# lower.net
KiCad netlist of a schematic drawn in EAGLE
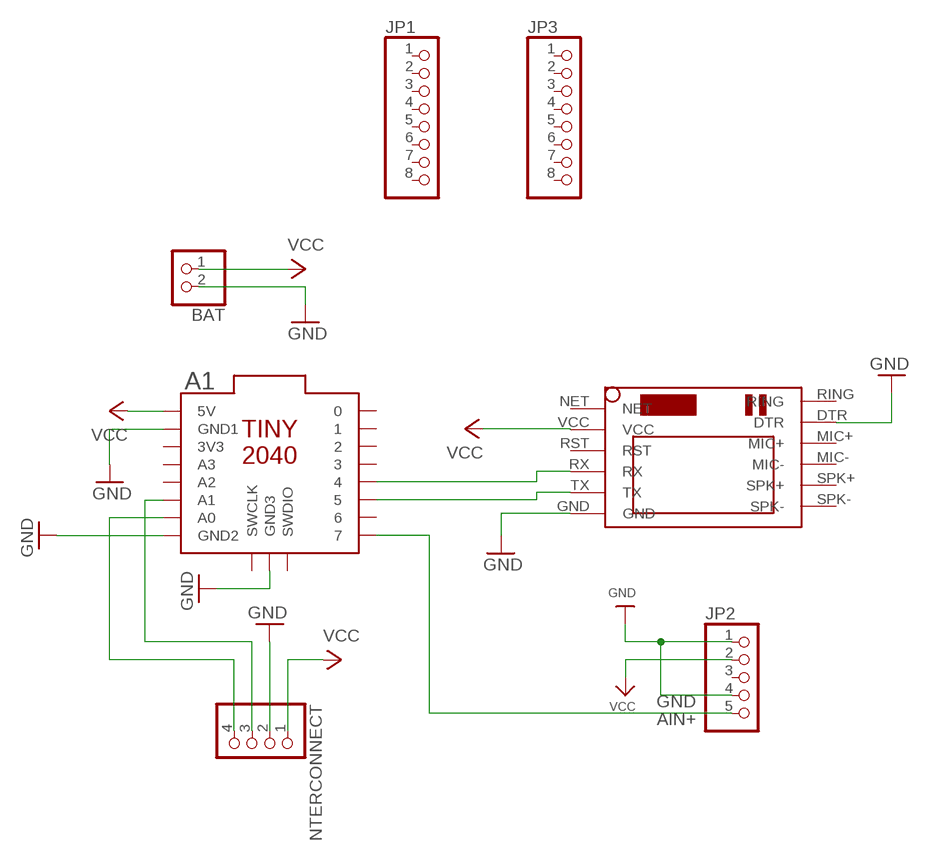
[diagram p0: schematic, sheet 1]

(export (version "E")
  (design (tool "Eeschema 10.0.6"))
  (components
    (comp (ref "A1")
      (value "TINY2040")
      (footprint "eagle-import:TINY2040")
      (libsource (lib "eagle-import") (part "TINY2040"))
    )
    (comp (ref "BAT")
      (value "JST_2PIN-THM-RA")
      (footprint "eagle-import:JST-PH-2-THM-RA")
      (libsource (lib "eagle-import") (part "JST_2PIN-THM-RA"))
    )
    (comp (ref "INTERCONNECT")
      (value "PINHD-1X4")
      (footprint "eagle-import:1X04")
      (libsource (lib "eagle-import") (part "PINHD-1X4"))
    )
    (comp (ref "JP1")
      (value "PINHD-1X8")
      (footprint "eagle-import:1X08")
      (libsource (lib "eagle-import") (part "PINHD-1X8"))
    )
    (comp (ref "JP2")
      (value "HEADER-1X570MIL")
      (footprint "eagle-import:1X05_ROUND_70")
      (libsource (lib "eagle-import") (part "HEADER-1X570MIL"))
    )
    (comp (ref "JP3")
      (value "PINHD-1X8")
      (footprint "eagle-import:1X08")
      (libsource (lib "eagle-import") (part "PINHD-1X8"))
    )
    (comp (ref "U$2")
      (value "SIM800LMODULE")
      (footprint "eagle-import:SIM800LMODULE")
      (libsource (lib "eagle-import") (part "SIM800LMODULE"))
    )
  )
  (nets
    (net (code "1") (name "/AIN+") (class "Default")
      (node (ref "A1") (pin "7") (pinfunction "7_7") (pintype "bidirectional"))
      (node (ref "JP2") (pin "5") (pinfunction "5_5") (pintype "passive"))
    )
    (net (code "2") (name "GND") (class "Default")
      (node (ref "A1") (pin "GND1") (pinfunction "GND1_GND1") (pintype "bidirectional"))
      (node (ref "A1") (pin "GND2") (pinfunction "GND2_GND2") (pintype "bidirectional"))
      (node (ref "A1") (pin "GND3") (pinfunction "GND3_GND3") (pintype "bidirectional"))
      (node (ref "BAT") (pin "2") (pinfunction "1_2") (pintype "passive"))
      (node (ref "INTERCONNECT") (pin "2") (pinfunction "2_2") (pintype "passive"))
      (node (ref "JP2") (pin "1") (pinfunction "1_1") (pintype "passive"))
      (node (ref "JP2") (pin "4") (pinfunction "4_4") (pintype "passive"))
      (node (ref "U$2") (pin "DTR") (pinfunction "DTR_DTR") (pintype "bidirectional"))
      (node (ref "U$2") (pin "GND") (pinfunction "GND_GND") (pintype "bidirectional"))
    )
    (net (code "3") (name "Net-(A1-Pad4)") (class "Default")
      (node (ref "A1") (pin "4") (pinfunction "4_4") (pintype "bidirectional"))
      (node (ref "U$2") (pin "RX") (pinfunction "RX_RX") (pintype "bidirectional"))
    )
    (net (code "4") (name "Net-(A1-Pad5)") (class "Default")
      (node (ref "A1") (pin "5") (pinfunction "5_5") (pintype "bidirectional"))
      (node (ref "U$2") (pin "TX") (pinfunction "TX_TX") (pintype "bidirectional"))
    )
    (net (code "5") (name "Net-(A1-PadA0)") (class "Default")
      (node (ref "A1") (pin "A0") (pinfunction "A0_A0") (pintype "bidirectional"))
      (node (ref "INTERCONNECT") (pin "4") (pinfunction "4_4") (pintype "passive"))
    )
    (net (code "6") (name "Net-(A1-PadA1)") (class "Default")
      (node (ref "A1") (pin "A1") (pinfunction "A1_A1") (pintype "bidirectional"))
      (node (ref "INTERCONNECT") (pin "3") (pinfunction "3_3") (pintype "passive"))
    )
    (net (code "7") (name "VCC") (class "Default")
      (node (ref "A1") (pin "5V") (pinfunction "5V_5V") (pintype "bidirectional"))
      (node (ref "BAT") (pin "1") (pinfunction "2_1") (pintype "passive"))
      (node (ref "INTERCONNECT") (pin "1") (pinfunction "1_1") (pintype "passive"))
      (node (ref "JP2") (pin "2") (pinfunction "2_2") (pintype "passive"))
      (node (ref "U$2") (pin "VCC") (pinfunction "VCC_VCC") (pintype "bidirectional"))
    )
    (net (code "8") (name "unconnected-(A1-Pad0)") (class "Default")
      (node (ref "A1") (pin "0") (pinfunction "0_0") (pintype "bidirectional"))
    )
    (net (code "9") (name "unconnected-(A1-Pad1)") (class "Default")
      (node (ref "A1") (pin "1") (pinfunction "1_1") (pintype "bidirectional"))
    )
    (net (code "10") (name "unconnected-(A1-Pad2)") (class "Default")
      (node (ref "A1") (pin "2") (pinfunction "2_2") (pintype "bidirectional"))
    )
    (net (code "11") (name "unconnected-(A1-Pad3)") (class "Default")
      (node (ref "A1") (pin "3") (pinfunction "3_3") (pintype "bidirectional"))
    )
    (net (code "12") (name "unconnected-(A1-Pad3V3)") (class "Default")
      (node (ref "A1") (pin "3V3") (pinfunction "3V3_3V3") (pintype "bidirectional"))
    )
    (net (code "13") (name "unconnected-(A1-Pad6)") (class "Default")
      (node (ref "A1") (pin "6") (pinfunction "6_6") (pintype "bidirectional"))
    )
    (net (code "14") (name "unconnected-(A1-PadA2)") (class "Default")
      (node (ref "A1") (pin "A2") (pinfunction "A2_A2") (pintype "bidirectional"))
    )
    (net (code "15") (name "unconnected-(A1-PadA3)") (class "Default")
      (node (ref "A1") (pin "A3") (pinfunction "A3_A3") (pintype "bidirectional"))
    )
    (net (code "16") (name "unconnected-(A1-PadSWCLK)") (class "Default")
      (node (ref "A1") (pin "SWCLK") (pinfunction "SWCLK_SWCLK") (pintype "bidirectional"))
    )
    (net (code "17") (name "unconnected-(A1-PadSWDIO)") (class "Default")
      (node (ref "A1") (pin "SWDIO") (pinfunction "SWDIO_SWDIO") (pintype "bidirectional"))
    )
    (net (code "18") (name "unconnected-(JP1-Pad1)") (class "Default")
      (node (ref "JP1") (pin "1") (pinfunction "1_1") (pintype "passive"))
    )
    (net (code "19") (name "unconnected-(JP1-Pad2)") (class "Default")
      (node (ref "JP1") (pin "2") (pinfunction "2_2") (pintype "passive"))
    )
    (net (code "20") (name "unconnected-(JP1-Pad3)") (class "Default")
      (node (ref "JP1") (pin "3") (pinfunction "3_3") (pintype "passive"))
    )
    (net (code "21") (name "unconnected-(JP1-Pad4)") (class "Default")
      (node (ref "JP1") (pin "4") (pinfunction "4_4") (pintype "passive"))
    )
    (net (code "22") (name "unconnected-(JP1-Pad5)") (class "Default")
      (node (ref "JP1") (pin "5") (pinfunction "5_5") (pintype "passive"))
    )
    (net (code "23") (name "unconnected-(JP1-Pad6)") (class "Default")
      (node (ref "JP1") (pin "6") (pinfunction "6_6") (pintype "passive"))
    )
    (net (code "24") (name "unconnected-(JP1-Pad7)") (class "Default")
      (node (ref "JP1") (pin "7") (pinfunction "7_7") (pintype "passive"))
    )
    (net (code "25") (name "unconnected-(JP1-Pad8)") (class "Default")
      (node (ref "JP1") (pin "8") (pinfunction "8_8") (pintype "passive"))
    )
    (net (code "26") (name "unconnected-(JP2-Pad3)") (class "Default")
      (node (ref "JP2") (pin "3") (pinfunction "3_3") (pintype "passive"))
    )
    (net (code "27") (name "unconnected-(JP3-Pad1)") (class "Default")
      (node (ref "JP3") (pin "1") (pinfunction "1_1") (pintype "passive"))
    )
    (net (code "28") (name "unconnected-(JP3-Pad2)") (class "Default")
      (node (ref "JP3") (pin "2") (pinfunction "2_2") (pintype "passive"))
    )
    (net (code "29") (name "unconnected-(JP3-Pad3)") (class "Default")
      (node (ref "JP3") (pin "3") (pinfunction "3_3") (pintype "passive"))
    )
    (net (code "30") (name "unconnected-(JP3-Pad4)") (class "Default")
      (node (ref "JP3") (pin "4") (pinfunction "4_4") (pintype "passive"))
    )
    (net (code "31") (name "unconnected-(JP3-Pad5)") (class "Default")
      (node (ref "JP3") (pin "5") (pinfunction "5_5") (pintype "passive"))
    )
    (net (code "32") (name "unconnected-(JP3-Pad6)") (class "Default")
      (node (ref "JP3") (pin "6") (pinfunction "6_6") (pintype "passive"))
    )
    (net (code "33") (name "unconnected-(JP3-Pad7)") (class "Default")
      (node (ref "JP3") (pin "7") (pinfunction "7_7") (pintype "passive"))
    )
    (net (code "34") (name "unconnected-(JP3-Pad8)") (class "Default")
      (node (ref "JP3") (pin "8") (pinfunction "8_8") (pintype "passive"))
    )
    (net (code "35") (name "unconnected-(U$2-PadMIC+)") (class "Default")
      (node (ref "U$2") (pin "MIC+") (pinfunction "MIC+_MIC+") (pintype "bidirectional"))
    )
    (net (code "36") (name "unconnected-(U$2-PadMIC-)") (class "Default")
      (node (ref "U$2") (pin "MIC-") (pinfunction "MIC-_MIC-") (pintype "bidirectional"))
    )
    (net (code "37") (name "unconnected-(U$2-PadNET)") (class "Default")
      (node (ref "U$2") (pin "NET") (pinfunction "NET_NET") (pintype "bidirectional"))
    )
    (net (code "38") (name "unconnected-(U$2-PadRING)") (class "Default")
      (node (ref "U$2") (pin "RING") (pinfunction "RING_RING") (pintype "bidirectional"))
    )
    (net (code "39") (name "unconnected-(U$2-PadRST)") (class "Default")
      (node (ref "U$2") (pin "RST") (pinfunction "RST_RST") (pintype "bidirectional"))
    )
    (net (code "40") (name "unconnected-(U$2-PadSPK+)") (class "Default")
      (node (ref "U$2") (pin "SPK+") (pinfunction "SPK+_SPK+") (pintype "bidirectional"))
    )
    (net (code "41") (name "unconnected-(U$2-PadSPK-)") (class "Default")
      (node (ref "U$2") (pin "SPK-") (pinfunction "SPK-_SPK-") (pintype "bidirectional"))
    )
  )
)
